# ProProject_stm32_2023-08-13_1.net
KiCad netlist of a schematic drawn in EasyEDA Pro
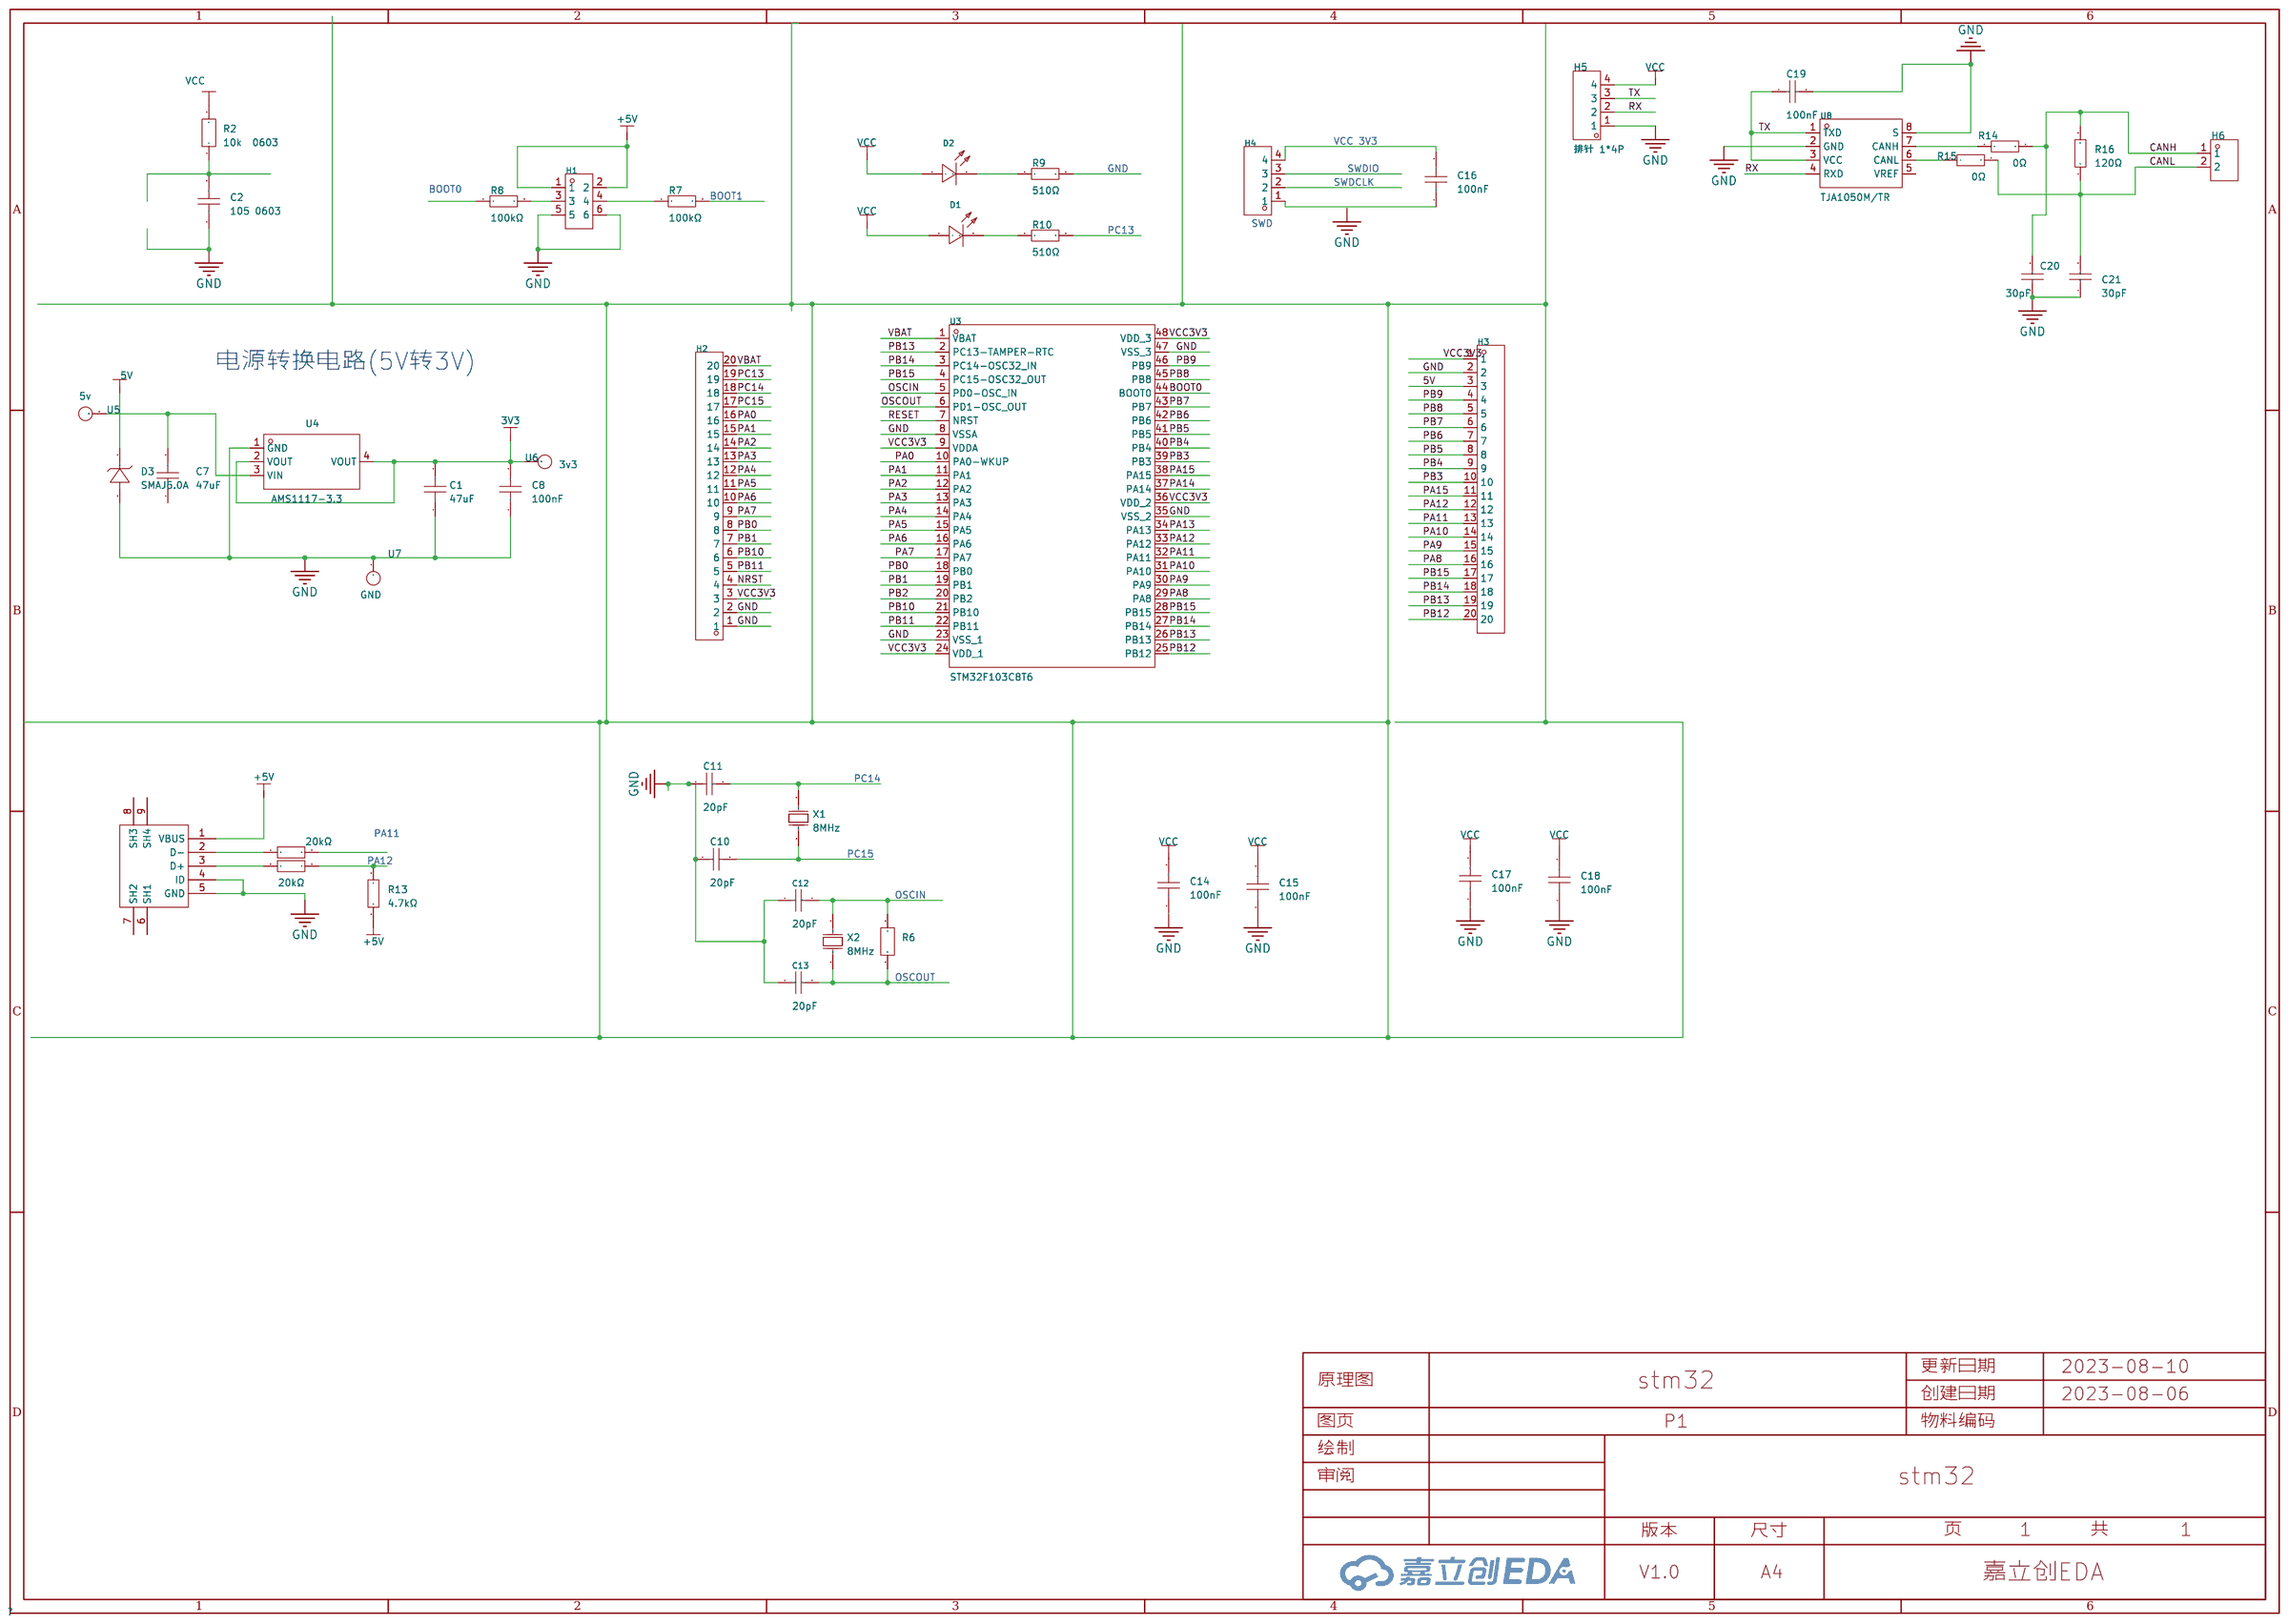
[diagram p0: schematic sheet]

(export (version "E")
  (design (tool "Eeschema 10.0.6"))
  (components
    (comp (ref "C1")
      (value "47uF")
      (footprint "easyedapro:C1206")
      (description "容值:47uF;精度:±20%;额定电压:16V;材质(温度系数):X5R;")
      (fields
        (field (name "Manufacturer Part") "GRM31CR61C476ME44L")
        (field (name "Manufacturer") "muRata(村田)")
      )
      (libsource (lib "easyedapro") (part "GRM31CR61C476ME44L"))
    )
    (comp (ref "C2")
      (value "105 0603")
      (footprint "easyedapro:C0805")
      (libsource (lib "easyedapro") (part "CapAcitance"))
    )
    (comp (ref "C7")
      (value "47uF")
      (footprint "easyedapro:C1206")
      (description "容值:47uF;精度:±20%;额定电压:16V;材质(温度系数):X5R;")
      (fields
        (field (name "Manufacturer Part") "GRM31CR61C476ME44L")
        (field (name "Manufacturer") "muRata(村田)")
      )
      (libsource (lib "easyedapro") (part "GRM31CR61C476ME44L"))
    )
    (comp (ref "C8")
      (value "100nF")
      (footprint "easyedapro:C0603")
      (description "容值:100nF;精度:±10%;额定电压:50V;材质(温度系数):X7R;")
      (fields
        (field (name "Manufacturer Part") "CC0603KRX7R9BB104")
        (field (name "Manufacturer") "YAGEO(国巨)")
      )
      (libsource (lib "easyedapro") (part "CC0603KRX7R9BB104"))
    )
    (comp (ref "C10")
      (value "20pF")
      (footprint "easyedapro:C0603")
      (description "容值:20pF;精度:±5%;额定电压:50V;材质(温度系数):C0G;")
      (fields
        (field (name "Manufacturer Part") "CL10C200JB8NNNC")
        (field (name "Manufacturer") "SAMSUNG(三星)")
      )
      (libsource (lib "easyedapro") (part "CL10C200JB8NNNC"))
    )
    (comp (ref "C11")
      (value "20pF")
      (footprint "easyedapro:C0603")
      (description "容值:20pF;精度:±5%;额定电压:50V;材质(温度系数):C0G;")
      (fields
        (field (name "Manufacturer Part") "CL10C200JB8NNNC")
        (field (name "Manufacturer") "SAMSUNG(三星)")
      )
      (libsource (lib "easyedapro") (part "CL10C200JB8NNNC"))
    )
    (comp (ref "C12")
      (value "20pF")
      (footprint "easyedapro:C0402")
      (description "容值:20pF;精度:±5%;额定电压:50V;材质(温度系数):C0G;")
      (fields (field (name "Manufacturer Part") "0402CG200J500NT") (field (name "Manufacturer") "FH(风华)"))
      (libsource (lib "easyedapro") (part "0402CG200J500NT"))
    )
    (comp (ref "C13")
      (value "20pF")
      (footprint "easyedapro:C0402")
      (description "容值:20pF;精度:±5%;额定电压:50V;材质(温度系数):C0G;")
      (fields (field (name "Manufacturer Part") "0402CG200J500NT") (field (name "Manufacturer") "FH(风华)"))
      (libsource (lib "easyedapro") (part "0402CG200J500NT"))
    )
    (comp (ref "C14")
      (value "100nF")
      (footprint "easyedapro:C0603")
      (description "容值:100nF;精度:±10%;额定电压:50V;材质(温度系数):X7R;")
      (fields
        (field (name "Manufacturer Part") "CC0603KRX7R9BB104")
        (field (name "Manufacturer") "YAGEO(国巨)")
      )
      (libsource (lib "easyedapro") (part "CC0603KRX7R9BB104"))
    )
    (comp (ref "C15")
      (value "100nF")
      (footprint "easyedapro:C0603")
      (description "容值:100nF;精度:±10%;额定电压:50V;材质(温度系数):X7R;")
      (fields
        (field (name "Manufacturer Part") "CC0603KRX7R9BB104")
        (field (name "Manufacturer") "YAGEO(国巨)")
      )
      (libsource (lib "easyedapro") (part "CC0603KRX7R9BB104"))
    )
    (comp (ref "C16")
      (value "100nF")
      (footprint "easyedapro:C0603")
      (description "容值:100nF;精度:±10%;额定电压:50V;材质(温度系数):X7R;")
      (fields
        (field (name "Manufacturer Part") "CC0603KRX7R9BB104")
        (field (name "Manufacturer") "YAGEO(国巨)")
      )
      (libsource (lib "easyedapro") (part "CC0603KRX7R9BB104"))
    )
    (comp (ref "C17")
      (value "100nF")
      (footprint "easyedapro:C0603")
      (description "容值:100nF;精度:±10%;额定电压:50V;材质(温度系数):X7R;")
      (fields
        (field (name "Manufacturer Part") "CC0603KRX7R9BB104")
        (field (name "Manufacturer") "YAGEO(国巨)")
      )
      (libsource (lib "easyedapro") (part "CC0603KRX7R9BB104"))
    )
    (comp (ref "C18")
      (value "100nF")
      (footprint "easyedapro:C0603")
      (description "容值:100nF;精度:±10%;额定电压:50V;材质(温度系数):X7R;")
      (fields
        (field (name "Manufacturer Part") "CC0603KRX7R9BB104")
        (field (name "Manufacturer") "YAGEO(国巨)")
      )
      (libsource (lib "easyedapro") (part "CC0603KRX7R9BB104"))
    )
    (comp (ref "C19")
      (value "100nF")
      (footprint "easyedapro:C0603")
      (description "容值:100nF;精度:±10%;额定电压:25V;材质(温度系数):X7R;")
      (fields
        (field (name "Manufacturer Part") "CC0603KRX7R8BB104")
        (field (name "Manufacturer") "YAGEO(国巨)")
      )
      (libsource (lib "easyedapro") (part "CC0603KRX7R8BB104"))
    )
    (comp (ref "C20")
      (value "30pF")
      (footprint "easyedapro:C0603")
      (description "容值:30pF;精度:±5%;额定电压:50V;材质(温度系数):C0G;")
      (fields (field (name "Manufacturer Part") "0603CG300J500NT") (field (name "Manufacturer") "FH(风华)"))
      (libsource (lib "easyedapro") (part "0603CG300J500NT"))
    )
    (comp (ref "C21")
      (value "30pF")
      (footprint "easyedapro:C0603")
      (description "容值:30pF;精度:±5%;额定电压:50V;材质(温度系数):C0G;")
      (fields (field (name "Manufacturer Part") "0603CG300J500NT") (field (name "Manufacturer") "FH(风华)"))
      (libsource (lib "easyedapro") (part "0603CG300J500NT"))
    )
    (comp (ref "D1")
      (value "KT-0805W")
      (footprint "easyedapro:LED0805-R-RD")
      (description "色温6000K左右")
      (fields (field (name "Manufacturer") "KENTO"))
      (libsource (lib "easyedapro") (part "whiteLEDSMD"))
    )
    (comp (ref "D2")
      (value "KT-0805W")
      (footprint "easyedapro:LED0805-R-RD")
      (description "色温6000K左右")
      (fields (field (name "Manufacturer") "KENTO"))
      (libsource (lib "easyedapro") (part "whiteLEDSMD"))
    )
    (comp (ref "D3")
      (value "SMAJ5.0A")
      (footprint "easyedapro:SMA_L4.3-W2.6-LS5.0-RD")
      (fields (field (name "Manufacturer") "FUXINSEMI(富芯森美)"))
      (libsource (lib "easyedapro") (part "SMAJ5.0A_C908198"))
    )
    (comp (ref "H1")
      (value "双排针2*3P 脚距2.54mm 贴片")
      (footprint "easyedapro:HDR-SMD_6P-P2.54-V-M-R2-C3-S2.54-LS7.4")
      (fields (field (name "Manufacturer") "BOOMELE(博穆精密)"))
      (libsource (lib "easyedapro") (part "双排针2*3P  脚距2.54MM  贴片"))
    )
    (comp (ref "H2")
      (value "PZ200-1-20-Z")
      (footprint "easyedapro:HDR-TH_20P-P2.00-V-M")
      (fields (field (name "Manufacturer") "HCTL(华灿天禄)"))
      (libsource (lib "easyedapro") (part "PZ200-1-20-Z"))
    )
    (comp (ref "H3")
      (value "PZ200-1-20-Z")
      (footprint "easyedapro:HDR-TH_20P-P2.00-V-M")
      (fields (field (name "Manufacturer") "HCTL(华灿天禄)"))
      (libsource (lib "easyedapro") (part "PZ200-1-20-Z"))
    )
    (comp (ref "H4")
      (value "PZ200-1-04-Z")
      (footprint "easyedapro:HDR-TH_4P-P2.00-V-M")
      (fields (field (name "Manufacturer") "HCTL(华灿天禄)"))
      (libsource (lib "easyedapro") (part "PZ200-1-04-Z"))
    )
    (comp (ref "H5")
      (value "排针 1*4P")
      (footprint "easyedapro:HDR-TH_4P-P2.54-V-M")
      (libsource (lib "easyedapro") (part "Header-Male-2.54_1x4_C59481"))
    )
    (comp (ref "H6")
      (value "2.0双塑排针1*2p 总针长11mm两边3+4")
      (footprint "easyedapro:HDR-TH_2P-P2.00-V-M-3")
      (libsource (lib "easyedapro") (part "2.0双塑排针1*2P 总针长11MM两边3+4"))
    )
    (comp (ref "R2")
      (value "10k  0603")
      (footprint "easyedapro:R0603")
      (description "电阻类型:薄膜电阻;阻值:10kΩ;精度:±0.05%;功率:100mW;")
      (fields
        (field (name "Manufacturer Part") "TNPU060310K0AZEN00")
        (field (name "Manufacturer") "VISHAY(威世)")
      )
      (libsource (lib "easyedapro") (part "TNPU060310K0AZEN00"))
    )
    (comp (ref "R6")
      (value "直插金属膜电阻1MΩ±1%1/2W")
      (footprint "easyedapro:RES-TH_BD3.5-L9.0-P13.00-D0.5")
      (libsource (lib "easyedapro") (part "直插金属膜电阻1MΩ±1%1/2W"))
    )
    (comp (ref "R7")
      (value "100kΩ")
      (footprint "easyedapro:R0603")
      (description "电阻类型:厚膜电阻;阻值:100kΩ;精度:±1%;功率:100mW;")
      (fields
        (field (name "Manufacturer Part") "0603WAF1003T5E")
        (field (name "Manufacturer") "UNI-ROYAL(厚声)")
      )
      (libsource (lib "easyedapro") (part "0603WAF1003T5E"))
    )
    (comp (ref "R8")
      (value "100kΩ")
      (footprint "easyedapro:R0603")
      (description "电阻类型:厚膜电阻;阻值:100kΩ;精度:±1%;功率:100mW;")
      (fields
        (field (name "Manufacturer Part") "0603WAF1003T5E")
        (field (name "Manufacturer") "UNI-ROYAL(厚声)")
      )
      (libsource (lib "easyedapro") (part "0603WAF1003T5E"))
    )
    (comp (ref "R9")
      (value "510Ω")
      (footprint "easyedapro:R0603")
      (description "电阻类型:厚膜电阻;阻值:510Ω;精度:±1%;功率:100mW;")
      (fields
        (field (name "Manufacturer Part") "0603WAF5100T5E")
        (field (name "Manufacturer") "UNI-ROYAL(厚声)")
      )
      (libsource (lib "easyedapro") (part "0603WAF5100T5E"))
    )
    (comp (ref "R10")
      (value "510Ω")
      (footprint "easyedapro:R0603")
      (description "电阻类型:厚膜电阻;阻值:510Ω;精度:±1%;功率:100mW;")
      (fields
        (field (name "Manufacturer Part") "0603WAF5100T5E")
        (field (name "Manufacturer") "UNI-ROYAL(厚声)")
      )
      (libsource (lib "easyedapro") (part "0603WAF5100T5E"))
    )
    (comp (ref "R11")
      (value "20kΩ")
      (footprint "easyedapro:R0603")
      (description "电阻类型:厚膜电阻;阻值:20kΩ;精度:±1%;功率:100mW;")
      (fields
        (field (name "Manufacturer Part") "0603WAF2002T5E")
        (field (name "Manufacturer") "UNI-ROYAL(厚声)")
      )
      (libsource (lib "easyedapro") (part "0603WAF2002T5E"))
    )
    (comp (ref "R12")
      (value "20kΩ")
      (footprint "easyedapro:R0603")
      (description "电阻类型:厚膜电阻;阻值:20kΩ;精度:±1%;功率:100mW;")
      (fields
        (field (name "Manufacturer Part") "0603WAF2002T5E")
        (field (name "Manufacturer") "UNI-ROYAL(厚声)")
      )
      (libsource (lib "easyedapro") (part "0603WAF2002T5E"))
    )
    (comp (ref "R13")
      (value "4.7kΩ")
      (footprint "easyedapro:R0603")
      (description "电阻类型:厚膜电阻;阻值:4.7kΩ;精度:±1%;功率:100mW;")
      (fields
        (field (name "Manufacturer Part") "0603WAF4701T5E")
        (field (name "Manufacturer") "UNI-ROYAL(厚声)")
      )
      (libsource (lib "easyedapro") (part "0603WAF4701T5E"))
    )
    (comp (ref "R14")
      (value "0Ω")
      (footprint "easyedapro:R0603")
      (description "电阻类型:厚膜电阻;阻值:0Ω;精度:±1%;功率:100mW;")
      (fields
        (field (name "Manufacturer Part") "0603WAF0000T5E")
        (field (name "Manufacturer") "UNI-ROYAL(厚声)")
      )
      (libsource (lib "easyedapro") (part "0603WAF0000T5E"))
    )
    (comp (ref "R15")
      (value "0Ω")
      (footprint "easyedapro:R0603")
      (description "电阻类型:厚膜电阻;阻值:0Ω;精度:±1%;功率:100mW;")
      (fields
        (field (name "Manufacturer Part") "0603WAF0000T5E")
        (field (name "Manufacturer") "UNI-ROYAL(厚声)")
      )
      (libsource (lib "easyedapro") (part "0603WAF0000T5E"))
    )
    (comp (ref "R16")
      (value "120Ω")
      (footprint "easyedapro:R0603")
      (description "电阻类型:厚膜电阻;阻值:120Ω;精度:±1%;功率:100mW;")
      (fields
        (field (name "Manufacturer Part") "0603WAF1200T5E")
        (field (name "Manufacturer") "UNI-ROYAL(厚声)")
      )
      (libsource (lib "easyedapro") (part "0603WAF1200T5E"))
    )
    (comp (ref "U3")
      (value "STM32F103C8T6")
      (footprint "easyedapro:LQFP-48_L7.0-W7.0-P0.50-LS9.0-BL")
      (fields (field (name "Manufacturer") "ST(意法半导体)"))
      (libsource (lib "easyedapro") (part "STM32F103C8T6"))
    )
    (comp (ref "U4")
      (value "AMS1117-3.3")
      (fields (field (name "Manufacturer") "AMS"))
      (libsource (lib "easyedapro") (part "ams1117-3.3"))
    )
    (comp (ref "U5")
      (value "5v")
      (footprint "easyedapro:测试点0.9mm")
      (libsource (lib "easyedapro") (part "测试点0.9mm"))
    )
    (comp (ref "U6")
      (value "3v3")
      (footprint "easyedapro:测试点0.9mm")
      (libsource (lib "easyedapro") (part "测试点0.9mm"))
    )
    (comp (ref "U7")
      (value "GND")
      (footprint "easyedapro:测试点0.9mm")
      (libsource (lib "easyedapro") (part "测试点0.9mm"))
    )
    (comp (ref "U8")
      (value "TJA1050M/TR")
      (footprint "easyedapro:SOIC-8_L4.9-W3.9-P1.27-LS6.0-BL")
      (description "CAN芯片  1Mbps 5V供电，110节点，高速总线接收器")
      (fields (field (name "Manufacturer") "HGSEMI(华冠)"))
      (libsource (lib "easyedapro") (part "TJA1050M/TR"))
    )
    (comp (ref "USB1")
      (value "MicroXNJ")
      (footprint "easyedapro:MICRO-USB-SMD_MICROXNJ")
      (description "连接器类型:Micro-B;标准:USB 2.0;公母:母座;触点数量:5P;端口数量:1;安装方式:卧贴;额定电流 - 电源:1A;工作温度范围:-20°C~+85°C;")
      (fields (field (name "Manufacturer") "SHOU HAN(首韩)"))
      (libsource (lib "easyedapro") (part "MICROXNJ"))
    )
    (comp (ref "X1")
      (value "8MHz")
      (footprint "easyedapro:CRYSTAL-SMD_L11.5-W4.8-LS12.7")
      (description "频率:8MHz;频率公差:±20ppm;负载电容:20pF;")
      (fields (field (name "Manufacturer Part") "X49SM8MSD2SC") (field (name "Manufacturer") "YXC(扬兴晶振)"))
      (libsource (lib "easyedapro") (part "X49SM8MSD2SC"))
    )
    (comp (ref "X2")
      (value "8MHz")
      (footprint "easyedapro:CRYSTAL-SMD_L11.5-W4.8-LS12.7")
      (description "频率:8MHz;频率公差:±20ppm;负载电容:20pF;")
      (fields (field (name "Manufacturer Part") "X49SM8MSD2SC") (field (name "Manufacturer") "YXC(扬兴晶振)"))
      (libsource (lib "easyedapro") (part "X49SM8MSD2SC"))
    )
  )
  (nets
    (net (code "1") (name "+5V") (class "Default")
      (node (ref "H1") (pin "1") (pinfunction "1_1") (pintype "input"))
      (node (ref "H1") (pin "2") (pinfunction "2_2") (pintype "input"))
      (node (ref "R13") (pin "1") (pinfunction "1_1") (pintype "input"))
      (node (ref "USB1") (pin "1") (pinfunction "VBUS_1") (pintype "input"))
    )
    (net (code "2") (name "/BOOT0") (class "Default")
      (node (ref "U3") (pin "44") (pinfunction "BOOT0_44") (pintype "input"))
    )
    (net (code "3") (name "/CANH") (class "Default")
      (node (ref "C20") (pin "2") (pinfunction "2_2") (pintype "input"))
      (node (ref "H6") (pin "1") (pinfunction "1_1") (pintype "input"))
      (node (ref "R14") (pin "2") (pinfunction "2_2") (pintype "input"))
      (node (ref "R16") (pin "2") (pinfunction "2_2") (pintype "input"))
    )
    (net (code "4") (name "/CANL") (class "Default")
      (node (ref "C21") (pin "2") (pinfunction "2_2") (pintype "input"))
      (node (ref "H6") (pin "2") (pinfunction "2_2") (pintype "input"))
      (node (ref "R15") (pin "2") (pinfunction "2_2") (pintype "input"))
      (node (ref "R16") (pin "1") (pinfunction "1_1") (pintype "input"))
    )
    (net (code "5") (name "/NRST") (class "Default")
      (node (ref "H2") (pin "4") (pinfunction "4_4") (pintype "input"))
    )
    (net (code "6") (name "/OSCIN") (class "Default")
      (node (ref "U3") (pin "5") (pinfunction "PD0-OSC_IN_5") (pintype "input"))
    )
    (net (code "7") (name "/OSCOUT") (class "Default")
      (node (ref "U3") (pin "6") (pinfunction "PD1-OSC_OUT_6") (pintype "input"))
    )
    (net (code "8") (name "/PA0") (class "Default")
      (node (ref "H2") (pin "16") (pinfunction "16_16") (pintype "input"))
      (node (ref "U3") (pin "10") (pinfunction "PA0-WKUP_10") (pintype "input"))
    )
    (net (code "9") (name "/PA1") (class "Default")
      (node (ref "H2") (pin "15") (pinfunction "15_15") (pintype "input"))
      (node (ref "U3") (pin "11") (pinfunction "PA1_11") (pintype "input"))
    )
    (net (code "10") (name "/PA2") (class "Default")
      (node (ref "H2") (pin "14") (pinfunction "14_14") (pintype "input"))
      (node (ref "U3") (pin "12") (pinfunction "PA2_12") (pintype "input"))
    )
    (net (code "11") (name "/PA3") (class "Default")
      (node (ref "H2") (pin "13") (pinfunction "13_13") (pintype "input"))
      (node (ref "U3") (pin "13") (pinfunction "PA3_13") (pintype "input"))
    )
    (net (code "12") (name "/PA4") (class "Default")
      (node (ref "H2") (pin "12") (pinfunction "12_12") (pintype "input"))
      (node (ref "U3") (pin "14") (pinfunction "PA4_14") (pintype "input"))
    )
    (net (code "13") (name "/PA5") (class "Default")
      (node (ref "H2") (pin "11") (pinfunction "11_11") (pintype "input"))
      (node (ref "U3") (pin "15") (pinfunction "PA5_15") (pintype "input"))
    )
    (net (code "14") (name "/PA6") (class "Default")
      (node (ref "H2") (pin "10") (pinfunction "10_10") (pintype "input"))
      (node (ref "U3") (pin "16") (pinfunction "PA6_16") (pintype "input"))
    )
    (net (code "15") (name "/PA7") (class "Default")
      (node (ref "H2") (pin "9") (pinfunction "9_9") (pintype "input"))
      (node (ref "U3") (pin "17") (pinfunction "PA7_17") (pintype "input"))
    )
    (net (code "16") (name "/PA8") (class "Default")
      (node (ref "H3") (pin "16") (pinfunction "16_16") (pintype "input"))
      (node (ref "U3") (pin "29") (pinfunction "PA8_29") (pintype "input"))
    )
    (net (code "17") (name "/PA9") (class "Default")
      (node (ref "H3") (pin "15") (pinfunction "15_15") (pintype "input"))
      (node (ref "U3") (pin "30") (pinfunction "PA9_30") (pintype "input"))
    )
    (net (code "18") (name "/PA10") (class "Default")
      (node (ref "H3") (pin "14") (pinfunction "14_14") (pintype "input"))
      (node (ref "U3") (pin "31") (pinfunction "PA10_31") (pintype "input"))
    )
    (net (code "19") (name "/PA11") (class "Default")
      (node (ref "H3") (pin "13") (pinfunction "13_13") (pintype "input"))
      (node (ref "U3") (pin "32") (pinfunction "PA11_32") (pintype "input"))
    )
    (net (code "20") (name "/PA12") (class "Default")
      (node (ref "H3") (pin "12") (pinfunction "12_12") (pintype "input"))
      (node (ref "U3") (pin "33") (pinfunction "PA12_33") (pintype "input"))
    )
    (net (code "21") (name "/PA13") (class "Default")
      (node (ref "U3") (pin "34") (pinfunction "PA13_34") (pintype "input"))
    )
    (net (code "22") (name "/PA14") (class "Default")
      (node (ref "U3") (pin "37") (pinfunction "PA14_37") (pintype "input"))
    )
    (net (code "23") (name "/PA15") (class "Default")
      (node (ref "H3") (pin "11") (pinfunction "11_11") (pintype "input"))
      (node (ref "U3") (pin "38") (pinfunction "PA15_38") (pintype "input"))
    )
    (net (code "24") (name "/PB0") (class "Default")
      (node (ref "H2") (pin "8") (pinfunction "8_8") (pintype "input"))
      (node (ref "U3") (pin "18") (pinfunction "PB0_18") (pintype "input"))
    )
    (net (code "25") (name "/PB1") (class "Default")
      (node (ref "H2") (pin "7") (pinfunction "7_7") (pintype "input"))
      (node (ref "U3") (pin "19") (pinfunction "PB1_19") (pintype "input"))
    )
    (net (code "26") (name "/PB2") (class "Default")
      (node (ref "U3") (pin "20") (pinfunction "PB2_20") (pintype "input"))
    )
    (net (code "27") (name "/PB3") (class "Default")
      (node (ref "H3") (pin "10") (pinfunction "10_10") (pintype "input"))
      (node (ref "U3") (pin "39") (pinfunction "PB3_39") (pintype "input"))
    )
    (net (code "28") (name "/PB4") (class "Default")
      (node (ref "H3") (pin "9") (pinfunction "9_9") (pintype "input"))
      (node (ref "U3") (pin "40") (pinfunction "PB4_40") (pintype "input"))
    )
    (net (code "29") (name "/PB5") (class "Default")
      (node (ref "H3") (pin "8") (pinfunction "8_8") (pintype "input"))
      (node (ref "U3") (pin "41") (pinfunction "PB5_41") (pintype "input"))
    )
    (net (code "30") (name "/PB6") (class "Default")
      (node (ref "H3") (pin "7") (pinfunction "7_7") (pintype "input"))
      (node (ref "U3") (pin "42") (pinfunction "PB6_42") (pintype "input"))
    )
    (net (code "31") (name "/PB7") (class "Default")
      (node (ref "H3") (pin "6") (pinfunction "6_6") (pintype "input"))
      (node (ref "U3") (pin "43") (pinfunction "PB7_43") (pintype "input"))
    )
    (net (code "32") (name "/PB8") (class "Default")
      (node (ref "H3") (pin "5") (pinfunction "5_5") (pintype "input"))
      (node (ref "U3") (pin "45") (pinfunction "PB8_45") (pintype "input"))
    )
    (net (code "33") (name "/PB9") (class "Default")
      (node (ref "H3") (pin "4") (pinfunction "4_4") (pintype "input"))
      (node (ref "U3") (pin "46") (pinfunction "PB9_46") (pintype "input"))
    )
    (net (code "34") (name "/PB10") (class "Default")
      (node (ref "H2") (pin "6") (pinfunction "6_6") (pintype "input"))
      (node (ref "U3") (pin "21") (pinfunction "PB10_21") (pintype "input"))
    )
    (net (code "35") (name "/PB11") (class "Default")
      (node (ref "H2") (pin "5") (pinfunction "5_5") (pintype "input"))
      (node (ref "U3") (pin "22") (pinfunction "PB11_22") (pintype "input"))
    )
    (net (code "36") (name "/PB12") (class "Default")
      (node (ref "H3") (pin "20") (pinfunction "20_20") (pintype "input"))
      (node (ref "U3") (pin "25") (pinfunction "PB12_25") (pintype "input"))
    )
    (net (code "37") (name "/PB13") (class "Default")
      (node (ref "H3") (pin "19") (pinfunction "19_19") (pintype "input"))
      (node (ref "U3") (pin "2") (pinfunction "PC13-TAMPER-RTC_2") (pintype "input"))
      (node (ref "U3") (pin "26") (pinfunction "PB13_26") (pintype "input"))
    )
    (net (code "38") (name "/PB14") (class "Default")
      (node (ref "H3") (pin "18") (pinfunction "18_18") (pintype "input"))
      (node (ref "U3") (pin "27") (pinfunction "PB14_27") (pintype "input"))
      (node (ref "U3") (pin "3") (pinfunction "PC14-OSC32_IN_3") (pintype "input"))
    )
    (net (code "39") (name "/PB15") (class "Default")
      (node (ref "H3") (pin "17") (pinfunction "17_17") (pintype "input"))
      (node (ref "U3") (pin "28") (pinfunction "PB15_28") (pintype "input"))
      (node (ref "U3") (pin "4") (pinfunction "PC15-OSC32_OUT_4") (pintype "input"))
    )
    (net (code "40") (name "/PC13") (class "Default")
      (node (ref "H2") (pin "19") (pinfunction "19_19") (pintype "input"))
    )
    (net (code "41") (name "/PC14") (class "Default")
      (node (ref "H2") (pin "18") (pinfunction "18_18") (pintype "input"))
    )
    (net (code "42") (name "/PC15") (class "Default")
      (node (ref "H2") (pin "17") (pinfunction "17_17") (pintype "input"))
    )
    (net (code "43") (name "/RESET") (class "Default")
      (node (ref "U3") (pin "7") (pinfunction "NRST_7") (pintype "input"))
    )
    (net (code "44") (name "/RX") (class "Default")
      (node (ref "H5") (pin "2") (pinfunction "2_2") (pintype "input"))
      (node (ref "U8") (pin "4") (pinfunction "RXD_4") (pintype "input"))
    )
    (net (code "45") (name "/TX") (class "Default")
      (node (ref "C19") (pin "1") (pinfunction "1_1") (pintype "input"))
      (node (ref "H5") (pin "3") (pinfunction "3_3") (pintype "input"))
      (node (ref "U8") (pin "1") (pinfunction "TXD_1") (pintype "input"))
      (node (ref "U8") (pin "3") (pinfunction "VCC_3") (pintype "input"))
    )
    (net (code "46") (name "/VBAT") (class "Default")
      (node (ref "H2") (pin "20") (pinfunction "20_20") (pintype "input"))
      (node (ref "U3") (pin "1") (pinfunction "VBAT_1") (pintype "input"))
    )
    (net (code "47") (name "/VCC3V3") (class "Default")
      (node (ref "H2") (pin "3") (pinfunction "3_3") (pintype "input"))
      (node (ref "H3") (pin "1") (pinfunction "1_1") (pintype "input"))
      (node (ref "U3") (pin "24") (pinfunction "VDD_1_24") (pintype "input"))
      (node (ref "U3") (pin "36") (pinfunction "VDD_2_36") (pintype "input"))
      (node (ref "U3") (pin "48") (pinfunction "VDD_3_48") (pintype "input"))
      (node (ref "U3") (pin "9") (pinfunction "VDDA_9") (pintype "input"))
    )
    (net (code "48") (name "3V3") (class "Default")
      (node (ref "C1") (pin "2") (pinfunction "2_2") (pintype "input"))
      (node (ref "C8") (pin "2") (pinfunction "2_2") (pintype "input"))
      (node (ref "U4") (pin "2") (pinfunction "VOUT_2") (pintype "input"))
      (node (ref "U4") (pin "4") (pinfunction "VOUT_4") (pintype "input"))
      (node (ref "U6") (pin "1") (pinfunction "Pin1_1") (pintype "input"))
    )
    (net (code "49") (name "5V") (class "Default")
      (node (ref "D3") (pin "1") (pinfunction "C_1") (pintype "input"))
      (node (ref "H3") (pin "3") (pinfunction "3_3") (pintype "input"))
    )
    (net (code "50") (name "GND") (class "Default")
      (node (ref "C1") (pin "1") (pinfunction "1_1") (pintype "input"))
      (node (ref "C10") (pin "1") (pinfunction "1_1") (pintype "input"))
      (node (ref "C11") (pin "1") (pinfunction "1_1") (pintype "input"))
      (node (ref "C12") (pin "1") (pinfunction "1_1") (pintype "input"))
      (node (ref "C13") (pin "1") (pinfunction "1_1") (pintype "input"))
      (node (ref "C14") (pin "1") (pinfunction "1_1") (pintype "input"))
      (node (ref "C15") (pin "1") (pinfunction "1_1") (pintype "input"))
      (node (ref "C17") (pin "1") (pinfunction "1_1") (pintype "input"))
      (node (ref "C18") (pin "1") (pinfunction "1_1") (pintype "input"))
      (node (ref "C19") (pin "2") (pinfunction "2_2") (pintype "input"))
      (node (ref "C2") (pin "1") (pinfunction "1_1") (pintype "input"))
      (node (ref "C20") (pin "1") (pinfunction "1_1") (pintype "input"))
      (node (ref "C21") (pin "1") (pinfunction "1_1") (pintype "input"))
      (node (ref "C8") (pin "1") (pinfunction "1_1") (pintype "input"))
      (node (ref "D3") (pin "2") (pinfunction "A_2") (pintype "input"))
      (node (ref "H1") (pin "5") (pinfunction "5_5") (pintype "input"))
      (node (ref "H1") (pin "6") (pinfunction "6_6") (pintype "input"))
      (node (ref "H2") (pin "1") (pinfunction "1_1") (pintype "input"))
      (node (ref "H2") (pin "2") (pinfunction "2_2") (pintype "input"))
      (node (ref "H3") (pin "2") (pinfunction "2_2") (pintype "input"))
      (node (ref "H5") (pin "1") (pinfunction "1_1") (pintype "input"))
      (node (ref "U3") (pin "23") (pinfunction "VSS_1_23") (pintype "input"))
      (node (ref "U3") (pin "35") (pinfunction "VSS_2_35") (pintype "input"))
      (node (ref "U3") (pin "47") (pinfunction "VSS_3_47") (pintype "input"))
      (node (ref "U3") (pin "8") (pinfunction "VSSA_8") (pintype "input"))
      (node (ref "U4") (pin "1") (pinfunction "GND_1") (pintype "input"))
      (node (ref "U7") (pin "1") (pinfunction "Pin1_1") (pintype "input"))
      (node (ref "U8") (pin "2") (pinfunction "GND_2") (pintype "input"))
      (node (ref "U8") (pin "8") (pinfunction "S_8") (pintype "input"))
      (node (ref "USB1") (pin "4") (pinfunction "ID_4") (pintype "input"))
      (node (ref "USB1") (pin "5") (pinfunction "GND_5") (pintype "input"))
    )
    (net (code "51") (name "Net-(C2-Pad2)") (class "Default")
      (node (ref "C2") (pin "2") (pinfunction "2_2") (pintype "input"))
      (node (ref "R2") (pin "1") (pinfunction "1_1") (pintype "input"))
    )
    (net (code "52") (name "Net-(C16-Pad1)") (class "Default")
      (node (ref "C16") (pin "1") (pinfunction "1_1") (pintype "input"))
      (node (ref "H4") (pin "1") (pinfunction "1_1") (pintype "input"))
    )
    (net (code "53") (name "Net-(C16-Pad2)") (class "Default")
      (node (ref "C16") (pin "2") (pinfunction "2_2") (pintype "input"))
      (node (ref "H4") (pin "4") (pinfunction "4_4") (pintype "input"))
    )
    (net (code "54") (name "Net-(D1-K)") (class "Default")
      (node (ref "D1") (pin "2") (pinfunction "K_2") (pintype "input"))
      (node (ref "R10") (pin "1") (pinfunction "1_1") (pintype "input"))
    )
    (net (code "55") (name "Net-(D2-K)") (class "Default")
      (node (ref "D2") (pin "2") (pinfunction "K_2") (pintype "input"))
      (node (ref "R9") (pin "1") (pinfunction "1_1") (pintype "input"))
    )
    (net (code "56") (name "Net-(H1-Pad3)") (class "Default")
      (node (ref "H1") (pin "3") (pinfunction "3_3") (pintype "input"))
      (node (ref "R8") (pin "2") (pinfunction "2_2") (pintype "input"))
    )
    (net (code "57") (name "Net-(H1-Pad4)") (class "Default")
      (node (ref "H1") (pin "4") (pinfunction "4_4") (pintype "input"))
      (node (ref "R7") (pin "1") (pinfunction "1_1") (pintype "input"))
    )
    (net (code "58") (name "Net-(R12-Pad2)") (class "Default")
      (node (ref "R12") (pin "2") (pinfunction "2_2") (pintype "input"))
      (node (ref "R13") (pin "2") (pinfunction "2_2") (pintype "input"))
    )
    (net (code "59") (name "Net-(U4-VIN)") (class "Default")
      (node (ref "C7") (pin "2") (pinfunction "2_2") (pintype "input"))
      (node (ref "U4") (pin "3") (pinfunction "VIN_3") (pintype "input"))
      (node (ref "U5") (pin "1") (pinfunction "Pin1_1") (pintype "input"))
    )
    (net (code "60") (name "Net-(U8-CANH)") (class "Default")
      (node (ref "R14") (pin "1") (pinfunction "1_1") (pintype "input"))
      (node (ref "U8") (pin "7") (pinfunction "CANH_7") (pintype "input"))
    )
    (net (code "61") (name "Net-(U8-CANL)") (class "Default")
      (node (ref "R15") (pin "1") (pinfunction "1_1") (pintype "input"))
      (node (ref "U8") (pin "6") (pinfunction "CANL_6") (pintype "input"))
    )
    (net (code "62") (name "Net-(USB1-D+)") (class "Default")
      (node (ref "R12") (pin "1") (pinfunction "1_1") (pintype "input"))
      (node (ref "USB1") (pin "3") (pinfunction "D+_3") (pintype "input"))
    )
    (net (code "63") (name "Net-(USB1-D-)") (class "Default")
      (node (ref "R11") (pin "1") (pinfunction "1_1") (pintype "input"))
      (node (ref "USB1") (pin "2") (pinfunction "D-_2") (pintype "input"))
    )
    (net (code "64") (name "Net-(X1-OSC1)") (class "Default")
      (node (ref "C11") (pin "2") (pinfunction "2_2") (pintype "input"))
      (node (ref "X1") (pin "1") (pinfunction "OSC1_1") (pintype "input"))
    )
    (net (code "65") (name "Net-(X1-OSC2)") (class "Default")
      (node (ref "C10") (pin "2") (pinfunction "2_2") (pintype "input"))
      (node (ref "X1") (pin "2") (pinfunction "OSC2_2") (pintype "input"))
    )
    (net (code "66") (name "Net-(X2-OSC1)") (class "Default")
      (node (ref "C12") (pin "2") (pinfunction "2_2") (pintype "input"))
      (node (ref "R6") (pin "2") (pinfunction "2_2") (pintype "input"))
      (node (ref "X2") (pin "1") (pinfunction "OSC1_1") (pintype "input"))
    )
    (net (code "67") (name "Net-(X2-OSC2)") (class "Default")
      (node (ref "C13") (pin "2") (pinfunction "2_2") (pintype "input"))
      (node (ref "R6") (pin "1") (pinfunction "1_1") (pintype "input"))
      (node (ref "X2") (pin "2") (pinfunction "OSC2_2") (pintype "input"))
    )
    (net (code "68") (name "VCC") (class "Default")
      (node (ref "C14") (pin "2") (pinfunction "2_2") (pintype "input"))
      (node (ref "C15") (pin "2") (pinfunction "2_2") (pintype "input"))
      (node (ref "C17") (pin "2") (pinfunction "2_2") (pintype "input"))
      (node (ref "C18") (pin "2") (pinfunction "2_2") (pintype "input"))
      (node (ref "D1") (pin "1") (pinfunction "A_1") (pintype "input"))
      (node (ref "D2") (pin "1") (pinfunction "A_1") (pintype "input"))
      (node (ref "H5") (pin "4") (pinfunction "4_4") (pintype "input"))
      (node (ref "R2") (pin "2") (pinfunction "2_2") (pintype "input"))
    )
    (net (code "69") (name "unconnected-(C7-Pad1)") (class "Default")
      (node (ref "C7") (pin "1") (pinfunction "1_1") (pintype "input"))
    )
    (net (code "70") (name "unconnected-(H4-Pad2)") (class "Default")
      (node (ref "H4") (pin "2") (pinfunction "2_2") (pintype "input"))
    )
    (net (code "71") (name "unconnected-(H4-Pad3)") (class "Default")
      (node (ref "H4") (pin "3") (pinfunction "3_3") (pintype "input"))
    )
    (net (code "72") (name "unconnected-(R7-Pad2)") (class "Default")
      (node (ref "R7") (pin "2") (pinfunction "2_2") (pintype "input"))
    )
    (net (code "73") (name "unconnected-(R8-Pad1)") (class "Default")
      (node (ref "R8") (pin "1") (pinfunction "1_1") (pintype "input"))
    )
    (net (code "74") (name "unconnected-(R9-Pad2)") (class "Default")
      (node (ref "R9") (pin "2") (pinfunction "2_2") (pintype "input"))
    )
    (net (code "75") (name "unconnected-(R10-Pad2)") (class "Default")
      (node (ref "R10") (pin "2") (pinfunction "2_2") (pintype "input"))
    )
    (net (code "76") (name "unconnected-(R11-Pad2)") (class "Default")
      (node (ref "R11") (pin "2") (pinfunction "2_2") (pintype "input"))
    )
    (net (code "77") (name "unconnected-(U8-VREF-Pad5)") (class "Default")
      (node (ref "U8") (pin "5") (pinfunction "VREF_5") (pintype "input"))
    )
    (net (code "78") (name "unconnected-(USB1-SH1-Pad6)") (class "Default")
      (node (ref "USB1") (pin "6") (pinfunction "SH1_6") (pintype "input"))
    )
    (net (code "79") (name "unconnected-(USB1-SH2-Pad7)") (class "Default")
      (node (ref "USB1") (pin "7") (pinfunction "SH2_7") (pintype "input"))
    )
    (net (code "80") (name "unconnected-(USB1-SH3-Pad8)") (class "Default")
      (node (ref "USB1") (pin "8") (pinfunction "SH3_8") (pintype "input"))
    )
    (net (code "81") (name "unconnected-(USB1-SH4-Pad9)") (class "Default")
      (node (ref "USB1") (pin "9") (pinfunction "SH4_9") (pintype "input"))
    )
  )
)
